# di.net
KiCad netlist of a schematic drawn in Altium Designer
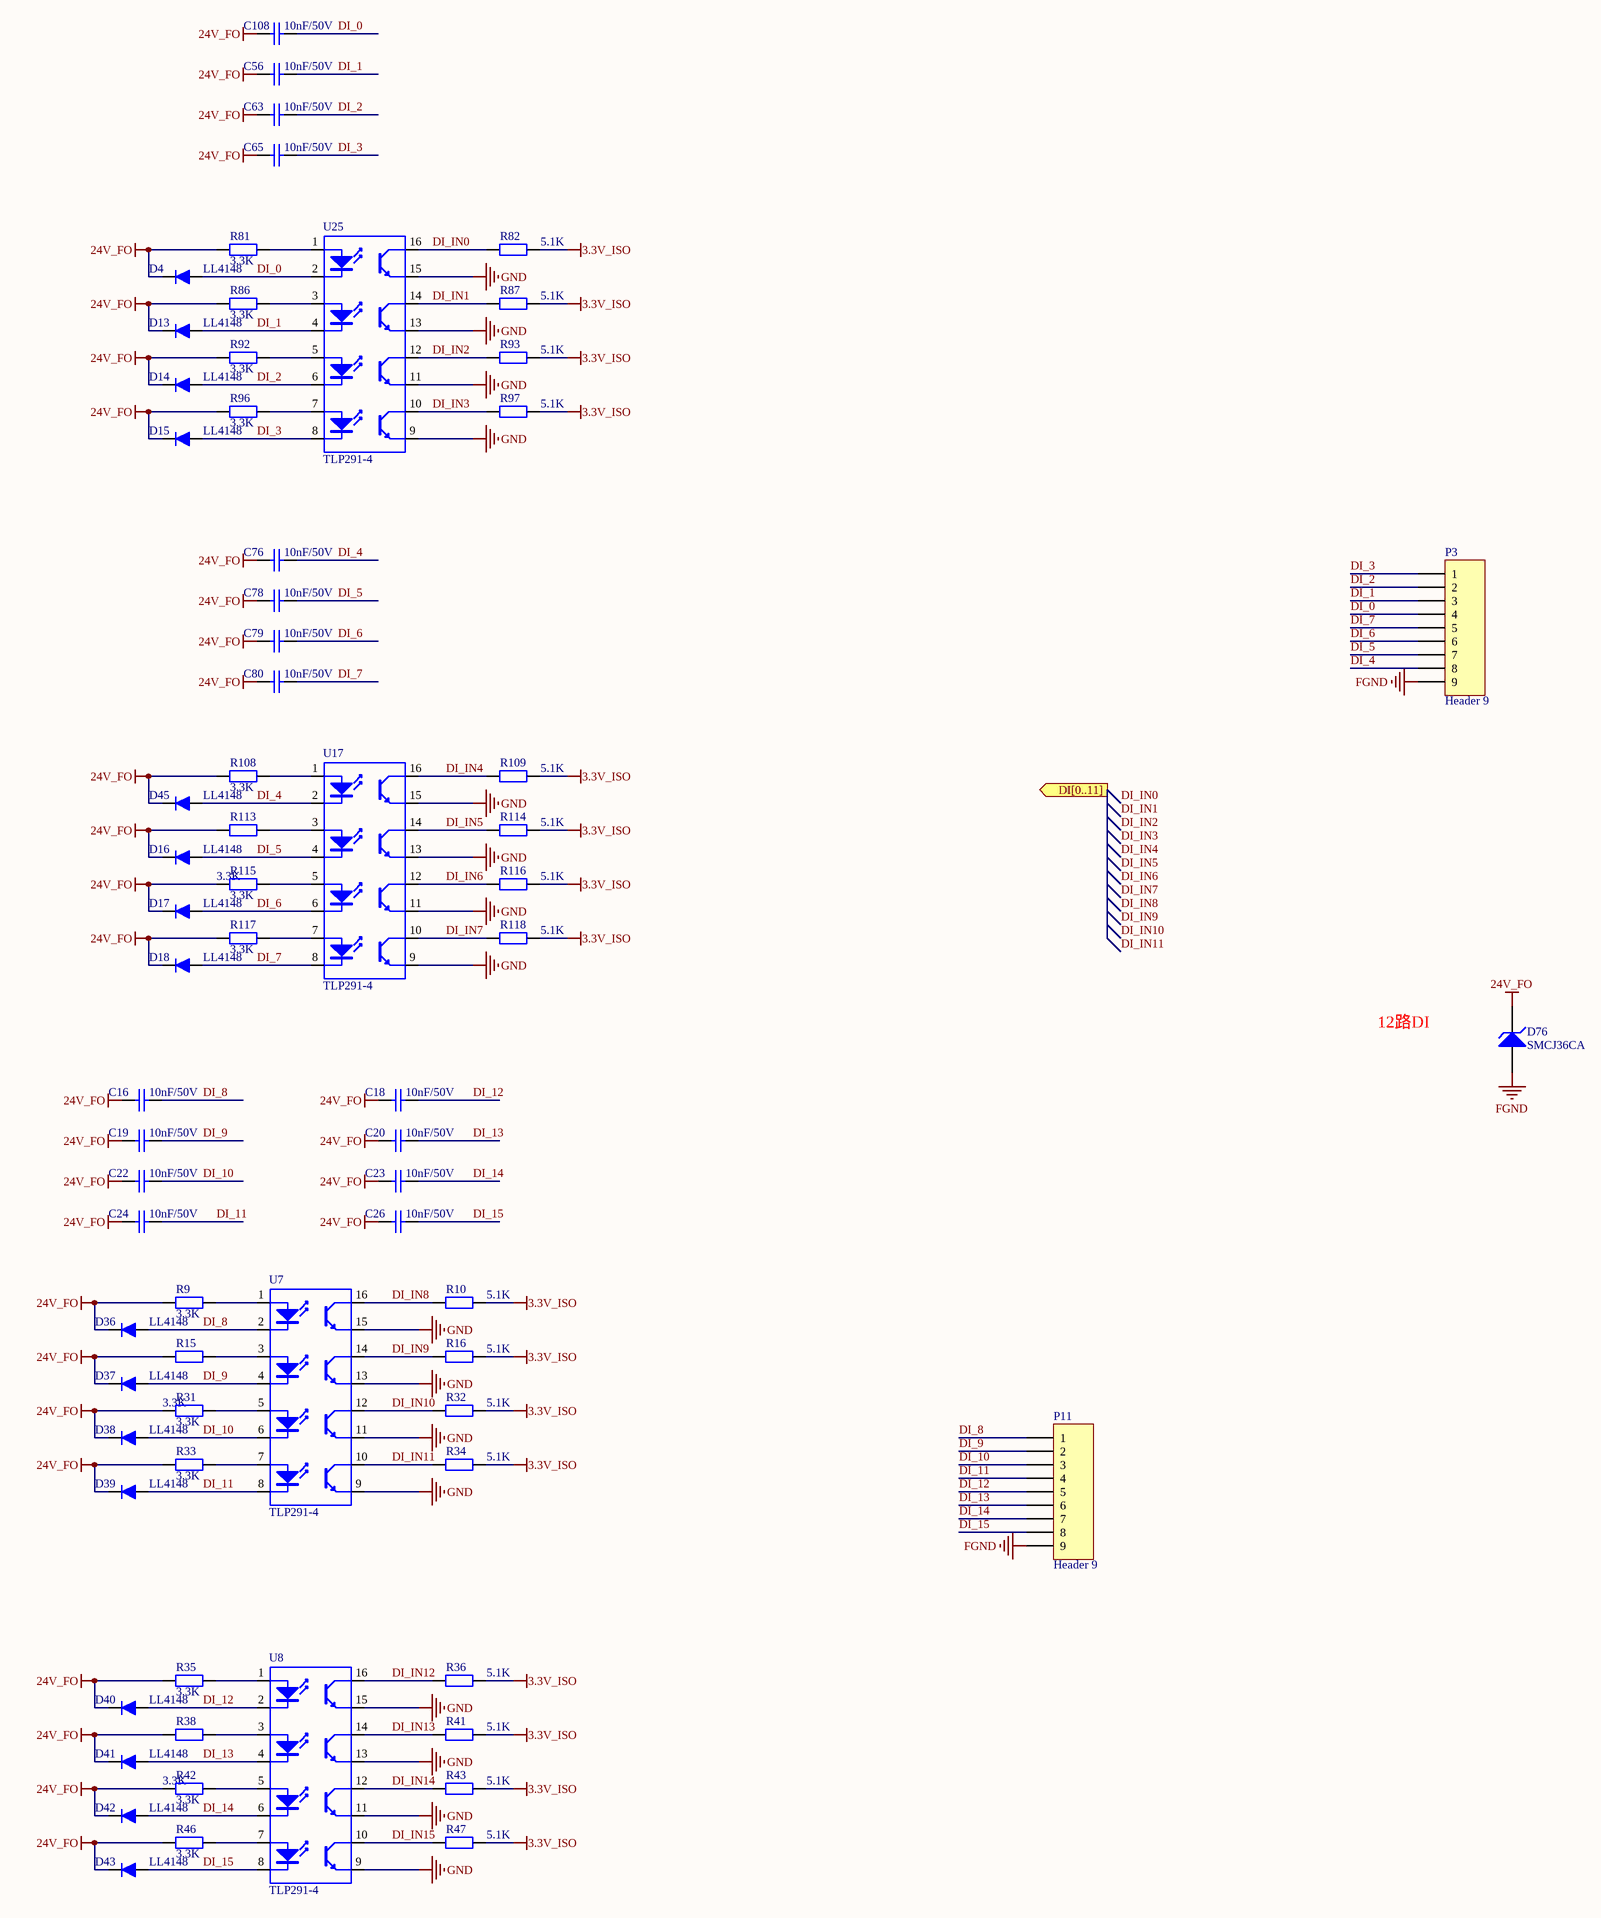
[diagram p0: di.SchDoc]

(export (version "E")
  (design (tool "Eeschema 10.0.6"))
  (components
    (comp (ref "C16")
      (value "10nF/50V")
      (footprint "0603C")
      (description "Capacitor")
      (fields (field (name "PUBLISHER") "Altium Limited"))
      (libsource (lib "Miscellaneous Devices") (part "Cap"))
    )
    (comp (ref "C18")
      (value "10nF/50V")
      (footprint "0603C")
      (description "Capacitor")
      (fields (field (name "PUBLISHER") "Altium Limited"))
      (libsource (lib "Miscellaneous Devices") (part "Cap"))
    )
    (comp (ref "C19")
      (value "10nF/50V")
      (footprint "0603C")
      (description "Capacitor")
      (fields (field (name "PUBLISHER") "Altium Limited"))
      (libsource (lib "Miscellaneous Devices") (part "Cap"))
    )
    (comp (ref "C20")
      (value "10nF/50V")
      (footprint "0603C")
      (description "Capacitor")
      (fields (field (name "PUBLISHER") "Altium Limited"))
      (libsource (lib "Miscellaneous Devices") (part "Cap"))
    )
    (comp (ref "C22")
      (value "10nF/50V")
      (footprint "0603C")
      (description "Capacitor")
      (fields (field (name "PUBLISHER") "Altium Limited"))
      (libsource (lib "Miscellaneous Devices") (part "Cap"))
    )
    (comp (ref "C23")
      (value "10nF/50V")
      (footprint "0603C")
      (description "Capacitor")
      (fields (field (name "PUBLISHER") "Altium Limited"))
      (libsource (lib "Miscellaneous Devices") (part "Cap"))
    )
    (comp (ref "C24")
      (value "10nF/50V")
      (footprint "0603C")
      (description "Capacitor")
      (fields (field (name "PUBLISHER") "Altium Limited"))
      (libsource (lib "Miscellaneous Devices") (part "Cap"))
    )
    (comp (ref "C26")
      (value "10nF/50V")
      (footprint "0603C")
      (description "Capacitor")
      (fields (field (name "PUBLISHER") "Altium Limited"))
      (libsource (lib "Miscellaneous Devices") (part "Cap"))
    )
    (comp (ref "C56")
      (value "10nF/50V")
      (footprint "0603C")
      (description "Capacitor")
      (fields (field (name "PUBLISHER") "Altium Limited"))
      (libsource (lib "Miscellaneous Devices") (part "Cap"))
    )
    (comp (ref "C63")
      (value "10nF/50V")
      (footprint "0603C")
      (description "Capacitor")
      (fields (field (name "PUBLISHER") "Altium Limited"))
      (libsource (lib "Miscellaneous Devices") (part "Cap"))
    )
    (comp (ref "C65")
      (value "10nF/50V")
      (footprint "0603C")
      (description "Capacitor")
      (fields (field (name "PUBLISHER") "Altium Limited"))
      (libsource (lib "Miscellaneous Devices") (part "Cap"))
    )
    (comp (ref "C76")
      (value "10nF/50V")
      (footprint "0603C")
      (description "Capacitor")
      (fields (field (name "PUBLISHER") "Altium Limited"))
      (libsource (lib "Miscellaneous Devices") (part "Cap"))
    )
    (comp (ref "C78")
      (value "10nF/50V")
      (footprint "0603C")
      (description "Capacitor")
      (fields (field (name "PUBLISHER") "Altium Limited"))
      (libsource (lib "Miscellaneous Devices") (part "Cap"))
    )
    (comp (ref "C79")
      (value "10nF/50V")
      (footprint "0603C")
      (description "Capacitor")
      (fields (field (name "PUBLISHER") "Altium Limited"))
      (libsource (lib "Miscellaneous Devices") (part "Cap"))
    )
    (comp (ref "C80")
      (value "10nF/50V")
      (footprint "0603C")
      (description "Capacitor")
      (fields (field (name "PUBLISHER") "Altium Limited"))
      (libsource (lib "Miscellaneous Devices") (part "Cap"))
    )
    (comp (ref "C108")
      (value "10nF/50V")
      (footprint "0603C")
      (description "Capacitor")
      (fields (field (name "PUBLISHER") "Altium Limited"))
      (libsource (lib "Miscellaneous Devices") (part "Cap"))
    )
    (comp (ref "D4")
      (value "LL4148")
      (footprint "DO-213AB/LL34/MiniMELF")
      (description "VISHAY,LL4148,圆柱体MiniMELF100V/2A,ROHS")
      (libsource (lib "Device2018") (part "LL4148"))
    )
    (comp (ref "D13")
      (value "LL4148")
      (footprint "DO-213AB/LL34/MiniMELF")
      (description "VISHAY,LL4148,圆柱体MiniMELF100V/2A,ROHS")
      (libsource (lib "Device2018") (part "LL4148"))
    )
    (comp (ref "D14")
      (value "LL4148")
      (footprint "DO-213AB/LL34/MiniMELF")
      (description "VISHAY,LL4148,圆柱体MiniMELF100V/2A,ROHS")
      (libsource (lib "Device2018") (part "LL4148"))
    )
    (comp (ref "D15")
      (value "LL4148")
      (footprint "DO-213AB/LL34/MiniMELF")
      (description "VISHAY,LL4148,圆柱体MiniMELF100V/2A,ROHS")
      (libsource (lib "Device2018") (part "LL4148"))
    )
    (comp (ref "D16")
      (value "LL4148")
      (footprint "DO-213AB/LL34/MiniMELF")
      (description "VISHAY,LL4148,圆柱体MiniMELF100V/2A,ROHS")
      (libsource (lib "Device2018") (part "LL4148"))
    )
    (comp (ref "D17")
      (value "LL4148")
      (footprint "DO-213AB/LL34/MiniMELF")
      (description "VISHAY,LL4148,圆柱体MiniMELF100V/2A,ROHS")
      (libsource (lib "Device2018") (part "LL4148"))
    )
    (comp (ref "D18")
      (value "LL4148")
      (footprint "DO-213AB/LL34/MiniMELF")
      (description "VISHAY,LL4148,圆柱体MiniMELF100V/2A,ROHS")
      (libsource (lib "Device2018") (part "LL4148"))
    )
    (comp (ref "D36")
      (value "LL4148")
      (footprint "DO-213AB/LL34/MiniMELF")
      (description "VISHAY,LL4148,圆柱体MiniMELF100V/2A,ROHS")
      (libsource (lib "Device2018") (part "LL4148"))
    )
    (comp (ref "D37")
      (value "LL4148")
      (footprint "DO-213AB/LL34/MiniMELF")
      (description "VISHAY,LL4148,圆柱体MiniMELF100V/2A,ROHS")
      (libsource (lib "Device2018") (part "LL4148"))
    )
    (comp (ref "D38")
      (value "LL4148")
      (footprint "DO-213AB/LL34/MiniMELF")
      (description "VISHAY,LL4148,圆柱体MiniMELF100V/2A,ROHS")
      (libsource (lib "Device2018") (part "LL4148"))
    )
    (comp (ref "D39")
      (value "LL4148")
      (footprint "DO-213AB/LL34/MiniMELF")
      (description "VISHAY,LL4148,圆柱体MiniMELF100V/2A,ROHS")
      (libsource (lib "Device2018") (part "LL4148"))
    )
    (comp (ref "D40")
      (value "LL4148")
      (footprint "DO-213AB/LL34/MiniMELF")
      (description "VISHAY,LL4148,圆柱体MiniMELF100V/2A,ROHS")
      (libsource (lib "Device2018") (part "LL4148"))
    )
    (comp (ref "D41")
      (value "LL4148")
      (footprint "DO-213AB/LL34/MiniMELF")
      (description "VISHAY,LL4148,圆柱体MiniMELF100V/2A,ROHS")
      (libsource (lib "Device2018") (part "LL4148"))
    )
    (comp (ref "D42")
      (value "LL4148")
      (footprint "DO-213AB/LL34/MiniMELF")
      (description "VISHAY,LL4148,圆柱体MiniMELF100V/2A,ROHS")
      (libsource (lib "Device2018") (part "LL4148"))
    )
    (comp (ref "D43")
      (value "LL4148")
      (footprint "DO-213AB/LL34/MiniMELF")
      (description "VISHAY,LL4148,圆柱体MiniMELF100V/2A,ROHS")
      (libsource (lib "Device2018") (part "LL4148"))
    )
    (comp (ref "D45")
      (value "LL4148")
      (footprint "DO-213AB/LL34/MiniMELF")
      (description "VISHAY,LL4148,圆柱体MiniMELF100V/2A,ROHS")
      (libsource (lib "Device2018") (part "LL4148"))
    )
    (comp (ref "D76")
      (value "SMCJ36CA")
      (footprint "smc")
      (description "SMBJ36CA")
      (fields (field (name "PUBLISHER") "Altium Limited"))
      (libsource (lib "Miscellaneous Devices") (part "D Zener"))
    )
    (comp (ref "P3")
      (value "Header 9")
      (footprint "2ETYR-5.08-09P-14-100")
      (description "Header, 9-Pin")
      (fields (field (name "PUBLISHER") "Altium Limited"))
      (libsource (lib "Miscellaneous Connectors") (part "Header 9"))
    )
    (comp (ref "P11")
      (value "Header 9")
      (footprint "2ETYR-5.08-09P-14-100")
      (description "Header, 9-Pin")
      (fields (field (name "PUBLISHER") "Altium Limited"))
      (libsource (lib "Miscellaneous Connectors") (part "Header 9"))
    )
    (comp (ref "R9") (value "3.3K") (footprint "0603R") (libsource (lib "MQlibrary") (part "Res0805M")))
    (comp (ref "R10") (value "5.1K") (footprint "0603R") (libsource (lib "MQlibrary") (part "Res0805M")))
    (comp (ref "R15") (value "3.3K") (footprint "0603R") (libsource (lib "MQlibrary") (part "Res0805M")))
    (comp (ref "R16") (value "5.1K") (footprint "0603R") (libsource (lib "MQlibrary") (part "Res0805M")))
    (comp (ref "R31") (value "3.3K") (footprint "0603R") (libsource (lib "MQlibrary") (part "Res0805M")))
    (comp (ref "R32") (value "5.1K") (footprint "0603R") (libsource (lib "MQlibrary") (part "Res0805M")))
    (comp (ref "R33") (value "3.3K") (footprint "0603R") (libsource (lib "MQlibrary") (part "Res0805M")))
    (comp (ref "R34") (value "5.1K") (footprint "0603R") (libsource (lib "MQlibrary") (part "Res0805M")))
    (comp (ref "R35") (value "3.3K") (footprint "0603R") (libsource (lib "MQlibrary") (part "Res0805M")))
    (comp (ref "R36") (value "5.1K") (footprint "0603R") (libsource (lib "MQlibrary") (part "Res0805M")))
    (comp (ref "R38") (value "3.3K") (footprint "0603R") (libsource (lib "MQlibrary") (part "Res0805M")))
    (comp (ref "R41") (value "5.1K") (footprint "0603R") (libsource (lib "MQlibrary") (part "Res0805M")))
    (comp (ref "R42") (value "3.3K") (footprint "0603R") (libsource (lib "MQlibrary") (part "Res0805M")))
    (comp (ref "R43") (value "5.1K") (footprint "0603R") (libsource (lib "MQlibrary") (part "Res0805M")))
    (comp (ref "R46") (value "3.3K") (footprint "0603R") (libsource (lib "MQlibrary") (part "Res0805M")))
    (comp (ref "R47") (value "5.1K") (footprint "0603R") (libsource (lib "MQlibrary") (part "Res0805M")))
    (comp (ref "R81") (value "3.3K") (footprint "0603R") (libsource (lib "MQlibrary") (part "Res0805M")))
    (comp (ref "R82") (value "5.1K") (footprint "0603R") (libsource (lib "MQlibrary") (part "Res0805M")))
    (comp (ref "R86") (value "3.3K") (footprint "0603R") (libsource (lib "MQlibrary") (part "Res0805M")))
    (comp (ref "R87") (value "5.1K") (footprint "0603R") (libsource (lib "MQlibrary") (part "Res0805M")))
    (comp (ref "R92") (value "3.3K") (footprint "0603R") (libsource (lib "MQlibrary") (part "Res0805M")))
    (comp (ref "R93") (value "5.1K") (footprint "0603R") (libsource (lib "MQlibrary") (part "Res0805M")))
    (comp (ref "R96") (value "3.3K") (footprint "0603R") (libsource (lib "MQlibrary") (part "Res0805M")))
    (comp (ref "R97") (value "5.1K") (footprint "0603R") (libsource (lib "MQlibrary") (part "Res0805M")))
    (comp (ref "R108") (value "3.3K") (footprint "0603R") (libsource (lib "MQlibrary") (part "Res0805M")))
    (comp (ref "R109") (value "5.1K") (footprint "0603R") (libsource (lib "MQlibrary") (part "Res0805M")))
    (comp (ref "R113") (value "3.3K") (footprint "0603R") (libsource (lib "MQlibrary") (part "Res0805M")))
    (comp (ref "R114") (value "5.1K") (footprint "0603R") (libsource (lib "MQlibrary") (part "Res0805M")))
    (comp (ref "R115") (value "3.3K") (footprint "0603R") (libsource (lib "MQlibrary") (part "Res0805M")))
    (comp (ref "R116") (value "5.1K") (footprint "0603R") (libsource (lib "MQlibrary") (part "Res0805M")))
    (comp (ref "R117") (value "3.3K") (footprint "0603R") (libsource (lib "MQlibrary") (part "Res0805M")))
    (comp (ref "R118") (value "5.1K") (footprint "0603R") (libsource (lib "MQlibrary") (part "Res0805M")))
    (comp (ref "U7") (value "TLP291-4") (footprint "SOP16-T") (libsource (lib "DI16") (part "TLP281-4")))
    (comp (ref "U8") (value "TLP291-4") (footprint "SOP16-T") (libsource (lib "DI16") (part "TLP281-4")))
    (comp (ref "U17") (value "TLP291-4") (footprint "SOP16-T") (libsource (lib "DI16") (part "TLP281-4")))
    (comp (ref "U25") (value "TLP291-4") (footprint "SOP16-T") (libsource (lib "DI16") (part "TLP281-4")))
  )
  (nets
    (net (code "14") (name "/DI_0") (class "Default")
      (node (ref "C108") (pin "2") (pinfunction "2_2") (pintype "passive"))
      (node (ref "D4") (pin "1") (pinfunction "2_1") (pintype "passive"))
      (node (ref "P3") (pin "4") (pinfunction "4_4") (pintype "passive"))
      (node (ref "U25") (pin "2") (pinfunction "K_2") (pintype "passive"))
    )
    (net (code "15") (name "/DI_1") (class "Default")
      (node (ref "C56") (pin "2") (pinfunction "2_2") (pintype "passive"))
      (node (ref "D13") (pin "1") (pinfunction "2_1") (pintype "passive"))
      (node (ref "P3") (pin "3") (pinfunction "3_3") (pintype "passive"))
      (node (ref "U25") (pin "4") (pinfunction "K_4") (pintype "passive"))
    )
    (net (code "16") (name "/DI_2") (class "Default")
      (node (ref "C63") (pin "2") (pinfunction "2_2") (pintype "passive"))
      (node (ref "D14") (pin "1") (pinfunction "2_1") (pintype "passive"))
      (node (ref "P3") (pin "2") (pinfunction "2_2") (pintype "passive"))
      (node (ref "U25") (pin "6") (pinfunction "K_6") (pintype "passive"))
    )
    (net (code "17") (name "/DI_3") (class "Default")
      (node (ref "C65") (pin "2") (pinfunction "2_2") (pintype "passive"))
      (node (ref "D15") (pin "1") (pinfunction "2_1") (pintype "passive"))
      (node (ref "P3") (pin "1") (pinfunction "1_1") (pintype "passive"))
      (node (ref "U25") (pin "8") (pinfunction "K_8") (pintype "passive"))
    )
    (net (code "18") (name "/DI_4") (class "Default")
      (node (ref "C76") (pin "2") (pinfunction "2_2") (pintype "passive"))
      (node (ref "D45") (pin "1") (pinfunction "2_1") (pintype "passive"))
      (node (ref "P3") (pin "8") (pinfunction "8_8") (pintype "passive"))
      (node (ref "U17") (pin "2") (pinfunction "K_2") (pintype "passive"))
    )
    (net (code "19") (name "/DI_5") (class "Default")
      (node (ref "C78") (pin "2") (pinfunction "2_2") (pintype "passive"))
      (node (ref "D16") (pin "1") (pinfunction "2_1") (pintype "passive"))
      (node (ref "P3") (pin "7") (pinfunction "7_7") (pintype "passive"))
      (node (ref "U17") (pin "4") (pinfunction "K_4") (pintype "passive"))
    )
    (net (code "20") (name "/DI_6") (class "Default")
      (node (ref "C79") (pin "2") (pinfunction "2_2") (pintype "passive"))
      (node (ref "D17") (pin "1") (pinfunction "2_1") (pintype "passive"))
      (node (ref "P3") (pin "6") (pinfunction "6_6") (pintype "passive"))
      (node (ref "U17") (pin "6") (pinfunction "K_6") (pintype "passive"))
    )
    (net (code "21") (name "/DI_7") (class "Default")
      (node (ref "C80") (pin "2") (pinfunction "2_2") (pintype "passive"))
      (node (ref "D18") (pin "1") (pinfunction "2_1") (pintype "passive"))
      (node (ref "P3") (pin "5") (pinfunction "5_5") (pintype "passive"))
      (node (ref "U17") (pin "8") (pinfunction "K_8") (pintype "passive"))
    )
    (net (code "22") (name "/DI_8") (class "Default")
      (node (ref "C16") (pin "2") (pinfunction "2_2") (pintype "passive"))
      (node (ref "D36") (pin "1") (pinfunction "2_1") (pintype "passive"))
      (node (ref "P11") (pin "1") (pinfunction "1_1") (pintype "passive"))
      (node (ref "U7") (pin "2") (pinfunction "K_2") (pintype "passive"))
    )
    (net (code "23") (name "/DI_9") (class "Default")
      (node (ref "C19") (pin "2") (pinfunction "2_2") (pintype "passive"))
      (node (ref "D37") (pin "1") (pinfunction "2_1") (pintype "passive"))
      (node (ref "P11") (pin "2") (pinfunction "2_2") (pintype "passive"))
      (node (ref "U7") (pin "4") (pinfunction "K_4") (pintype "passive"))
    )
    (net (code "24") (name "/DI_10") (class "Default")
      (node (ref "C22") (pin "2") (pinfunction "2_2") (pintype "passive"))
      (node (ref "D38") (pin "1") (pinfunction "2_1") (pintype "passive"))
      (node (ref "P11") (pin "3") (pinfunction "3_3") (pintype "passive"))
      (node (ref "U7") (pin "6") (pinfunction "K_6") (pintype "passive"))
    )
    (net (code "25") (name "/DI_11") (class "Default")
      (node (ref "C24") (pin "2") (pinfunction "2_2") (pintype "passive"))
      (node (ref "D39") (pin "1") (pinfunction "2_1") (pintype "passive"))
      (node (ref "P11") (pin "4") (pinfunction "4_4") (pintype "passive"))
      (node (ref "U7") (pin "8") (pinfunction "K_8") (pintype "passive"))
    )
    (net (code "26") (name "/DI_12") (class "Default")
      (node (ref "C18") (pin "2") (pinfunction "2_2") (pintype "passive"))
      (node (ref "D40") (pin "1") (pinfunction "2_1") (pintype "passive"))
      (node (ref "P11") (pin "5") (pinfunction "5_5") (pintype "passive"))
      (node (ref "U8") (pin "2") (pinfunction "K_2") (pintype "passive"))
    )
    (net (code "27") (name "/DI_13") (class "Default")
      (node (ref "C20") (pin "2") (pinfunction "2_2") (pintype "passive"))
      (node (ref "D41") (pin "1") (pinfunction "2_1") (pintype "passive"))
      (node (ref "P11") (pin "6") (pinfunction "6_6") (pintype "passive"))
      (node (ref "U8") (pin "4") (pinfunction "K_4") (pintype "passive"))
    )
    (net (code "28") (name "/DI_14") (class "Default")
      (node (ref "C23") (pin "2") (pinfunction "2_2") (pintype "passive"))
      (node (ref "D42") (pin "1") (pinfunction "2_1") (pintype "passive"))
      (node (ref "P11") (pin "7") (pinfunction "7_7") (pintype "passive"))
      (node (ref "U8") (pin "6") (pinfunction "K_6") (pintype "passive"))
    )
    (net (code "29") (name "/DI_15") (class "Default")
      (node (ref "C26") (pin "2") (pinfunction "2_2") (pintype "passive"))
      (node (ref "D43") (pin "1") (pinfunction "2_1") (pintype "passive"))
      (node (ref "P11") (pin "8") (pinfunction "8_8") (pintype "passive"))
      (node (ref "U8") (pin "8") (pinfunction "K_8") (pintype "passive"))
    )
    (net (code "30") (name "/DI_IN0") (class "Default")
      (node (ref "R82") (pin "2") (pinfunction "2_2") (pintype "passive"))
      (node (ref "U25") (pin "16") (pinfunction "C_16") (pintype "passive"))
    )
    (net (code "31") (name "/DI_IN1") (class "Default")
      (node (ref "R87") (pin "2") (pinfunction "2_2") (pintype "passive"))
      (node (ref "U25") (pin "14") (pinfunction "C_14") (pintype "passive"))
    )
    (net (code "32") (name "/DI_IN2") (class "Default")
      (node (ref "R93") (pin "2") (pinfunction "2_2") (pintype "passive"))
      (node (ref "U25") (pin "12") (pinfunction "C_12") (pintype "passive"))
    )
    (net (code "33") (name "/DI_IN3") (class "Default")
      (node (ref "R97") (pin "2") (pinfunction "2_2") (pintype "passive"))
      (node (ref "U25") (pin "10") (pinfunction "C_10") (pintype "passive"))
    )
    (net (code "34") (name "/DI_IN4") (class "Default")
      (node (ref "R109") (pin "2") (pinfunction "2_2") (pintype "passive"))
      (node (ref "U17") (pin "16") (pinfunction "C_16") (pintype "passive"))
    )
    (net (code "35") (name "/DI_IN5") (class "Default")
      (node (ref "R114") (pin "2") (pinfunction "2_2") (pintype "passive"))
      (node (ref "U17") (pin "14") (pinfunction "C_14") (pintype "passive"))
    )
    (net (code "36") (name "/DI_IN6") (class "Default")
      (node (ref "R116") (pin "2") (pinfunction "2_2") (pintype "passive"))
      (node (ref "U17") (pin "12") (pinfunction "C_12") (pintype "passive"))
    )
    (net (code "37") (name "/DI_IN7") (class "Default")
      (node (ref "R118") (pin "2") (pinfunction "2_2") (pintype "passive"))
      (node (ref "U17") (pin "10") (pinfunction "C_10") (pintype "passive"))
    )
    (net (code "38") (name "/DI_IN8") (class "Default")
      (node (ref "R10") (pin "2") (pinfunction "2_2") (pintype "passive"))
      (node (ref "U7") (pin "16") (pinfunction "C_16") (pintype "passive"))
    )
    (net (code "39") (name "/DI_IN9") (class "Default")
      (node (ref "R16") (pin "2") (pinfunction "2_2") (pintype "passive"))
      (node (ref "U7") (pin "14") (pinfunction "C_14") (pintype "passive"))
    )
    (net (code "40") (name "/DI_IN10") (class "Default")
      (node (ref "R32") (pin "2") (pinfunction "2_2") (pintype "passive"))
      (node (ref "U7") (pin "12") (pinfunction "C_12") (pintype "passive"))
    )
    (net (code "41") (name "/DI_IN11") (class "Default")
      (node (ref "R34") (pin "2") (pinfunction "2_2") (pintype "passive"))
      (node (ref "U7") (pin "10") (pinfunction "C_10") (pintype "passive"))
    )
    (net (code "42") (name "/DI_IN12") (class "Default")
      (node (ref "R36") (pin "2") (pinfunction "2_2") (pintype "passive"))
      (node (ref "U8") (pin "16") (pinfunction "C_16") (pintype "passive"))
    )
    (net (code "43") (name "/DI_IN13") (class "Default")
      (node (ref "R41") (pin "2") (pinfunction "2_2") (pintype "passive"))
      (node (ref "U8") (pin "14") (pinfunction "C_14") (pintype "passive"))
    )
    (net (code "44") (name "/DI_IN14") (class "Default")
      (node (ref "R43") (pin "2") (pinfunction "2_2") (pintype "passive"))
      (node (ref "U8") (pin "12") (pinfunction "C_12") (pintype "passive"))
    )
    (net (code "45") (name "/DI_IN15") (class "Default")
      (node (ref "R47") (pin "2") (pinfunction "2_2") (pintype "passive"))
      (node (ref "U8") (pin "10") (pinfunction "C_10") (pintype "passive"))
    )
    (net (code "46") (name "3.3V_ISO") (class "Default")
      (node (ref "R10") (pin "1") (pinfunction "1_1") (pintype "passive"))
      (node (ref "R109") (pin "1") (pinfunction "1_1") (pintype "passive"))
      (node (ref "R114") (pin "1") (pinfunction "1_1") (pintype "passive"))
      (node (ref "R116") (pin "1") (pinfunction "1_1") (pintype "passive"))
      (node (ref "R118") (pin "1") (pinfunction "1_1") (pintype "passive"))
      (node (ref "R16") (pin "1") (pinfunction "1_1") (pintype "passive"))
      (node (ref "R32") (pin "1") (pinfunction "1_1") (pintype "passive"))
      (node (ref "R34") (pin "1") (pinfunction "1_1") (pintype "passive"))
      (node (ref "R36") (pin "1") (pinfunction "1_1") (pintype "passive"))
      (node (ref "R41") (pin "1") (pinfunction "1_1") (pintype "passive"))
      (node (ref "R43") (pin "1") (pinfunction "1_1") (pintype "passive"))
      (node (ref "R47") (pin "1") (pinfunction "1_1") (pintype "passive"))
      (node (ref "R82") (pin "1") (pinfunction "1_1") (pintype "passive"))
      (node (ref "R87") (pin "1") (pinfunction "1_1") (pintype "passive"))
      (node (ref "R93") (pin "1") (pinfunction "1_1") (pintype "passive"))
      (node (ref "R97") (pin "1") (pinfunction "1_1") (pintype "passive"))
    )
    (net (code "47") (name "24V_FO") (class "Default")
      (node (ref "C108") (pin "1") (pinfunction "1_1") (pintype "passive"))
      (node (ref "C16") (pin "1") (pinfunction "1_1") (pintype "passive"))
      (node (ref "C18") (pin "1") (pinfunction "1_1") (pintype "passive"))
      (node (ref "C19") (pin "1") (pinfunction "1_1") (pintype "passive"))
      (node (ref "C20") (pin "1") (pinfunction "1_1") (pintype "passive"))
      (node (ref "C22") (pin "1") (pinfunction "1_1") (pintype "passive"))
      (node (ref "C23") (pin "1") (pinfunction "1_1") (pintype "passive"))
      (node (ref "C24") (pin "1") (pinfunction "1_1") (pintype "passive"))
      (node (ref "C26") (pin "1") (pinfunction "1_1") (pintype "passive"))
      (node (ref "C56") (pin "1") (pinfunction "1_1") (pintype "passive"))
      (node (ref "C63") (pin "1") (pinfunction "1_1") (pintype "passive"))
      (node (ref "C65") (pin "1") (pinfunction "1_1") (pintype "passive"))
      (node (ref "C76") (pin "1") (pinfunction "1_1") (pintype "passive"))
      (node (ref "C78") (pin "1") (pinfunction "1_1") (pintype "passive"))
      (node (ref "C79") (pin "1") (pinfunction "1_1") (pintype "passive"))
      (node (ref "C80") (pin "1") (pinfunction "1_1") (pintype "passive"))
      (node (ref "D13") (pin "2") (pinfunction "1_2") (pintype "passive"))
      (node (ref "D14") (pin "2") (pinfunction "1_2") (pintype "passive"))
      (node (ref "D15") (pin "2") (pinfunction "1_2") (pintype "passive"))
      (node (ref "D16") (pin "2") (pinfunction "1_2") (pintype "passive"))
      (node (ref "D17") (pin "2") (pinfunction "1_2") (pintype "passive"))
      (node (ref "D18") (pin "2") (pinfunction "1_2") (pintype "passive"))
      (node (ref "D36") (pin "2") (pinfunction "1_2") (pintype "passive"))
      (node (ref "D37") (pin "2") (pinfunction "1_2") (pintype "passive"))
      (node (ref "D38") (pin "2") (pinfunction "1_2") (pintype "passive"))
      (node (ref "D39") (pin "2") (pinfunction "1_2") (pintype "passive"))
      (node (ref "D4") (pin "2") (pinfunction "1_2") (pintype "passive"))
      (node (ref "D40") (pin "2") (pinfunction "1_2") (pintype "passive"))
      (node (ref "D41") (pin "2") (pinfunction "1_2") (pintype "passive"))
      (node (ref "D42") (pin "2") (pinfunction "1_2") (pintype "passive"))
      (node (ref "D43") (pin "2") (pinfunction "1_2") (pintype "passive"))
      (node (ref "D45") (pin "2") (pinfunction "1_2") (pintype "passive"))
      (node (ref "D76") (pin "2") (pinfunction "K_2") (pintype "passive"))
      (node (ref "R108") (pin "2") (pinfunction "2_2") (pintype "passive"))
      (node (ref "R113") (pin "2") (pinfunction "2_2") (pintype "passive"))
      (node (ref "R115") (pin "2") (pinfunction "2_2") (pintype "passive"))
      (node (ref "R117") (pin "2") (pinfunction "2_2") (pintype "passive"))
      (node (ref "R15") (pin "2") (pinfunction "2_2") (pintype "passive"))
      (node (ref "R31") (pin "2") (pinfunction "2_2") (pintype "passive"))
      (node (ref "R33") (pin "2") (pinfunction "2_2") (pintype "passive"))
      (node (ref "R35") (pin "2") (pinfunction "2_2") (pintype "passive"))
      (node (ref "R38") (pin "2") (pinfunction "2_2") (pintype "passive"))
      (node (ref "R42") (pin "2") (pinfunction "2_2") (pintype "passive"))
      (node (ref "R46") (pin "2") (pinfunction "2_2") (pintype "passive"))
      (node (ref "R81") (pin "2") (pinfunction "2_2") (pintype "passive"))
      (node (ref "R86") (pin "2") (pinfunction "2_2") (pintype "passive"))
      (node (ref "R9") (pin "2") (pinfunction "2_2") (pintype "passive"))
      (node (ref "R92") (pin "2") (pinfunction "2_2") (pintype "passive"))
      (node (ref "R96") (pin "2") (pinfunction "2_2") (pintype "passive"))
    )
    (net (code "48") (name "FGND") (class "Default")
      (node (ref "D76") (pin "1") (pinfunction "A_1") (pintype "passive"))
      (node (ref "P11") (pin "9") (pinfunction "9_9") (pintype "passive"))
      (node (ref "P3") (pin "9") (pinfunction "9_9") (pintype "passive"))
    )
    (net (code "49") (name "GND") (class "Default")
      (node (ref "U17") (pin "11") (pinfunction "E_11") (pintype "passive"))
      (node (ref "U17") (pin "13") (pinfunction "E_13") (pintype "passive"))
      (node (ref "U17") (pin "15") (pinfunction "E_15") (pintype "passive"))
      (node (ref "U17") (pin "9") (pinfunction "E_9") (pintype "passive"))
      (node (ref "U25") (pin "11") (pinfunction "E_11") (pintype "passive"))
      (node (ref "U25") (pin "13") (pinfunction "E_13") (pintype "passive"))
      (node (ref "U25") (pin "15") (pinfunction "E_15") (pintype "passive"))
      (node (ref "U25") (pin "9") (pinfunction "E_9") (pintype "passive"))
      (node (ref "U7") (pin "11") (pinfunction "E_11") (pintype "passive"))
      (node (ref "U7") (pin "13") (pinfunction "E_13") (pintype "passive"))
      (node (ref "U7") (pin "15") (pinfunction "E_15") (pintype "passive"))
      (node (ref "U7") (pin "9") (pinfunction "E_9") (pintype "passive"))
      (node (ref "U8") (pin "11") (pinfunction "E_11") (pintype "passive"))
      (node (ref "U8") (pin "13") (pinfunction "E_13") (pintype "passive"))
      (node (ref "U8") (pin "15") (pinfunction "E_15") (pintype "passive"))
      (node (ref "U8") (pin "9") (pinfunction "E_9") (pintype "passive"))
    )
    (net (code "50") (name "Net-(R9-Pad1)") (class "Default")
      (node (ref "R9") (pin "1") (pinfunction "1_1") (pintype "passive"))
      (node (ref "U7") (pin "1") (pinfunction "A_1") (pintype "passive"))
    )
    (net (code "51") (name "Net-(R15-Pad1)") (class "Default")
      (node (ref "R15") (pin "1") (pinfunction "1_1") (pintype "passive"))
      (node (ref "U7") (pin "3") (pinfunction "A_3") (pintype "passive"))
    )
    (net (code "52") (name "Net-(R31-Pad1)") (class "Default")
      (node (ref "R31") (pin "1") (pinfunction "1_1") (pintype "passive"))
      (node (ref "U7") (pin "5") (pinfunction "A_5") (pintype "passive"))
    )
    (net (code "53") (name "Net-(R33-Pad1)") (class "Default")
      (node (ref "R33") (pin "1") (pinfunction "1_1") (pintype "passive"))
      (node (ref "U7") (pin "7") (pinfunction "A_7") (pintype "passive"))
    )
    (net (code "54") (name "Net-(R35-Pad1)") (class "Default")
      (node (ref "R35") (pin "1") (pinfunction "1_1") (pintype "passive"))
      (node (ref "U8") (pin "1") (pinfunction "A_1") (pintype "passive"))
    )
    (net (code "55") (name "Net-(R38-Pad1)") (class "Default")
      (node (ref "R38") (pin "1") (pinfunction "1_1") (pintype "passive"))
      (node (ref "U8") (pin "3") (pinfunction "A_3") (pintype "passive"))
    )
    (net (code "56") (name "Net-(R42-Pad1)") (class "Default")
      (node (ref "R42") (pin "1") (pinfunction "1_1") (pintype "passive"))
      (node (ref "U8") (pin "5") (pinfunction "A_5") (pintype "passive"))
    )
    (net (code "57") (name "Net-(R46-Pad1)") (class "Default")
      (node (ref "R46") (pin "1") (pinfunction "1_1") (pintype "passive"))
      (node (ref "U8") (pin "7") (pinfunction "A_7") (pintype "passive"))
    )
    (net (code "58") (name "Net-(R81-Pad1)") (class "Default")
      (node (ref "R81") (pin "1") (pinfunction "1_1") (pintype "passive"))
      (node (ref "U25") (pin "1") (pinfunction "A_1") (pintype "passive"))
    )
    (net (code "59") (name "Net-(R86-Pad1)") (class "Default")
      (node (ref "R86") (pin "1") (pinfunction "1_1") (pintype "passive"))
      (node (ref "U25") (pin "3") (pinfunction "A_3") (pintype "passive"))
    )
    (net (code "60") (name "Net-(R92-Pad1)") (class "Default")
      (node (ref "R92") (pin "1") (pinfunction "1_1") (pintype "passive"))
      (node (ref "U25") (pin "5") (pinfunction "A_5") (pintype "passive"))
    )
    (net (code "61") (name "Net-(R96-Pad1)") (class "Default")
      (node (ref "R96") (pin "1") (pinfunction "1_1") (pintype "passive"))
      (node (ref "U25") (pin "7") (pinfunction "A_7") (pintype "passive"))
    )
    (net (code "62") (name "Net-(R108-Pad1)") (class "Default")
      (node (ref "R108") (pin "1") (pinfunction "1_1") (pintype "passive"))
      (node (ref "U17") (pin "1") (pinfunction "A_1") (pintype "passive"))
    )
    (net (code "63") (name "Net-(R113-Pad1)") (class "Default")
      (node (ref "R113") (pin "1") (pinfunction "1_1") (pintype "passive"))
      (node (ref "U17") (pin "3") (pinfunction "A_3") (pintype "passive"))
    )
    (net (code "64") (name "Net-(R115-Pad1)") (class "Default")
      (node (ref "R115") (pin "1") (pinfunction "1_1") (pintype "passive"))
      (node (ref "U17") (pin "5") (pinfunction "A_5") (pintype "passive"))
    )
    (net (code "65") (name "Net-(R117-Pad1)") (class "Default")
      (node (ref "R117") (pin "1") (pinfunction "1_1") (pintype "passive"))
      (node (ref "U17") (pin "7") (pinfunction "A_7") (pintype "passive"))
    )
  )
)
